# vesta_IO_buffering.net
KiCad netlist of a schematic drawn in Altium Designer
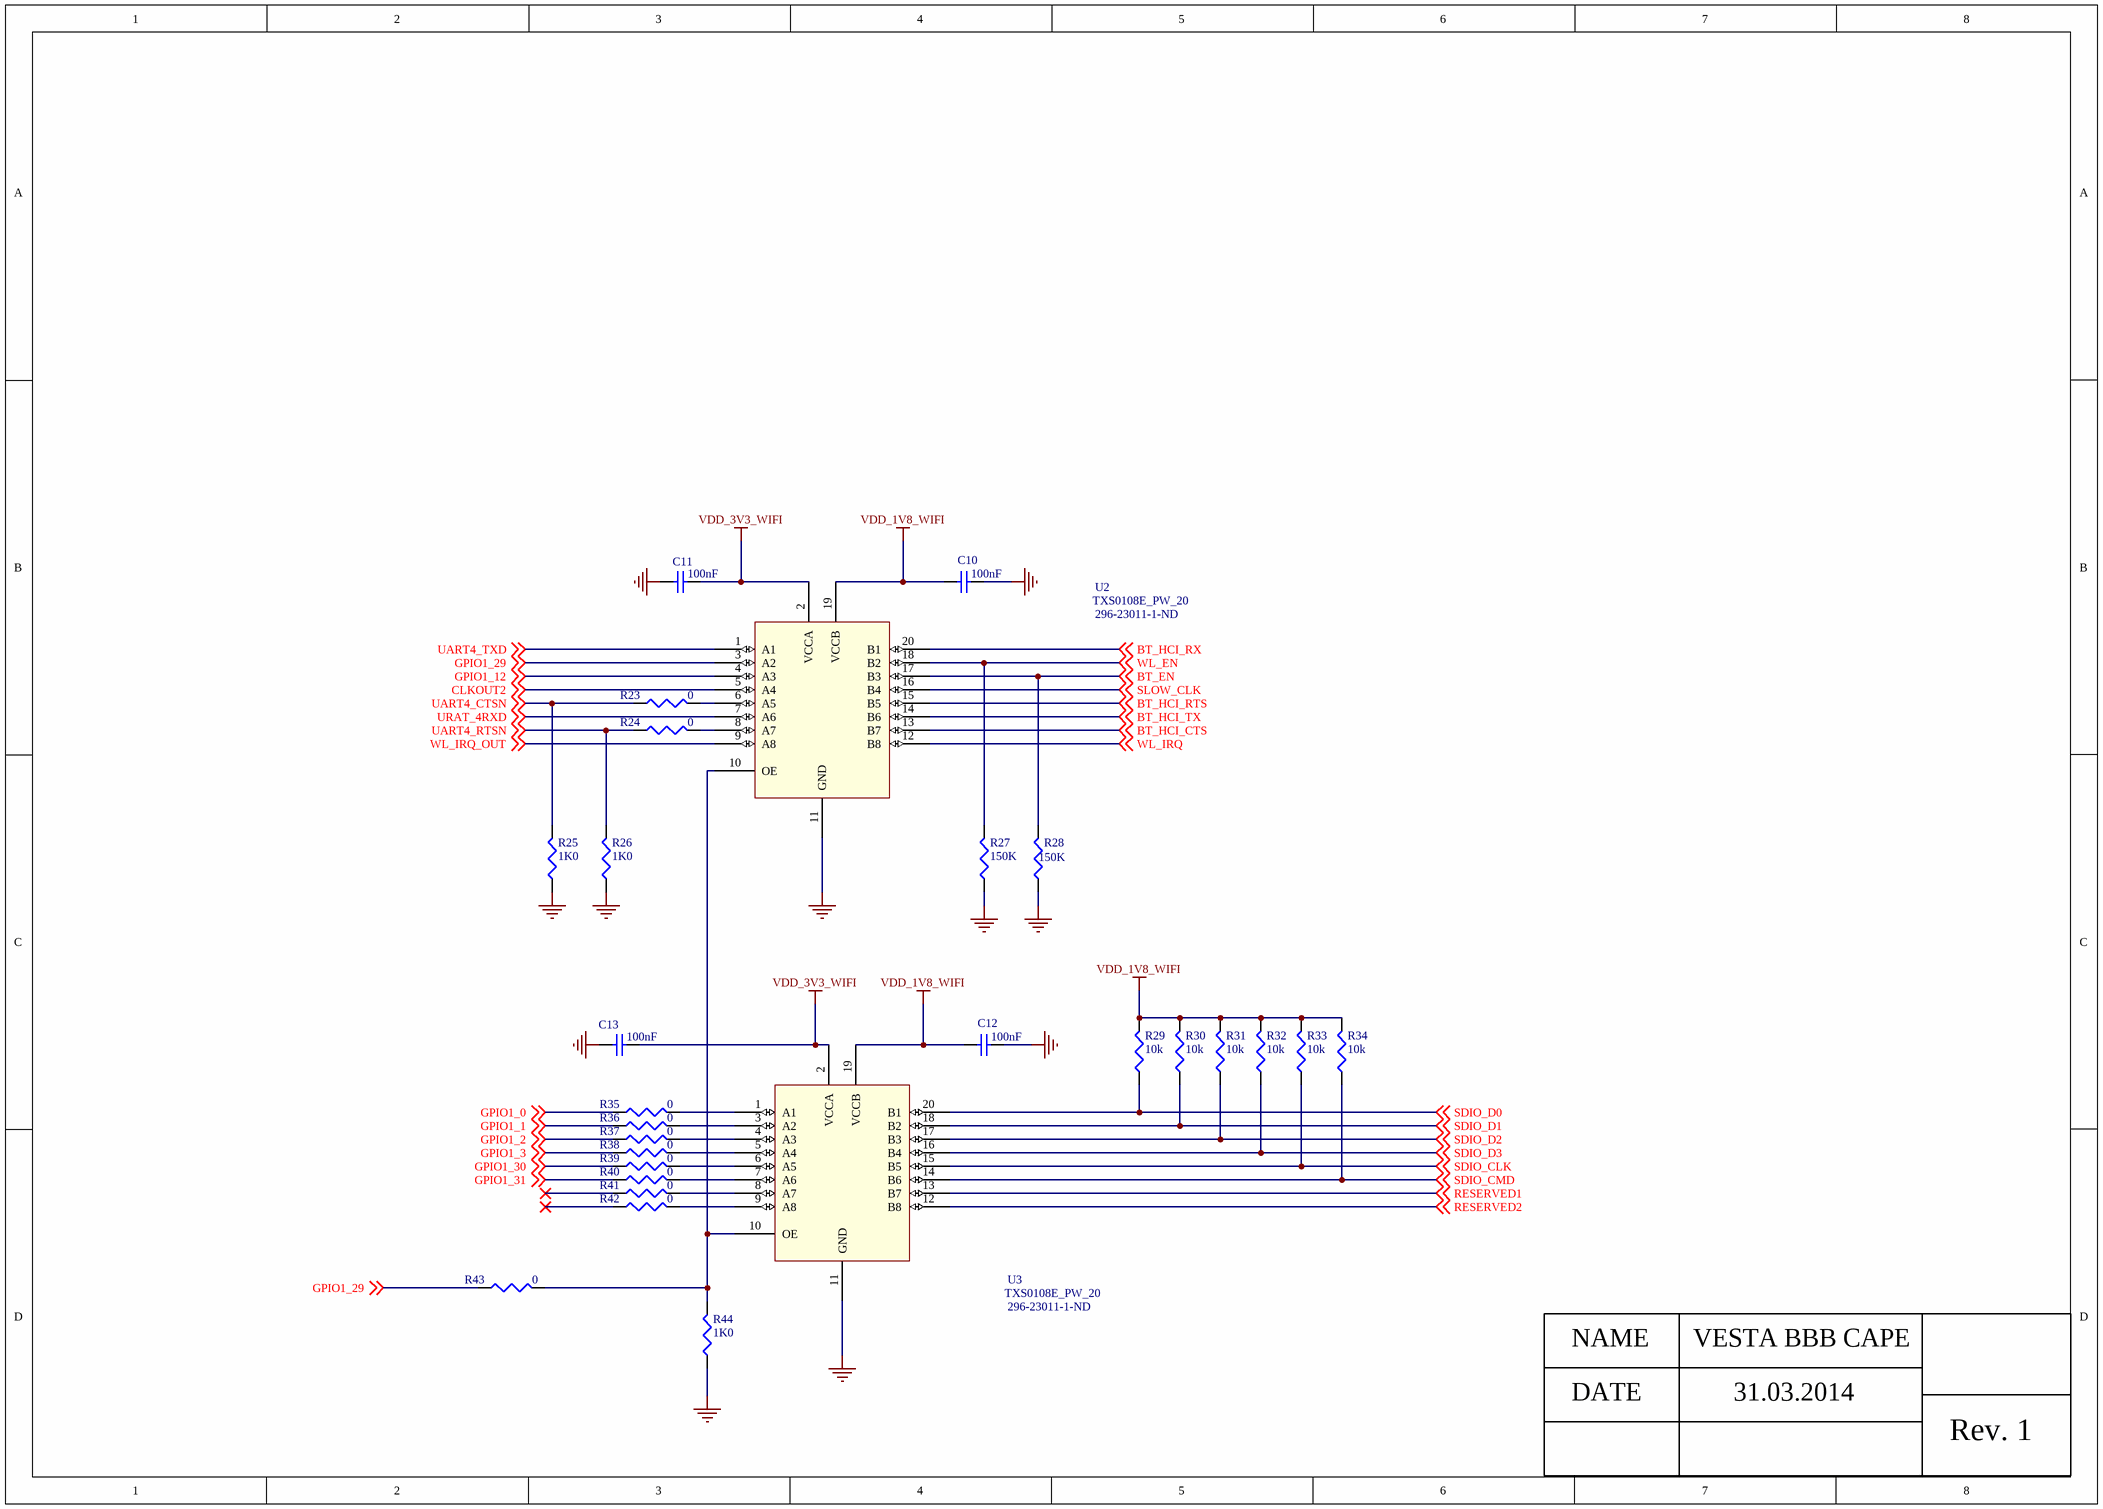
[diagram p0: vesta_IO_buffering.SchDoc]

(export (version "E")
  (design (tool "Eeschema 10.0.6"))
  (components
    (comp (ref "C10")
      (value "100nF")
      (footprint "C2512")
      (description "Capacitor (Semiconductor SIM Model)")
      (fields (field (name "Comment") "Cap Semi") (field (name "PUBLISHER") "Altium Limited"))
      (libsource (lib "Miscellaneous Devices") (part "Cap Semi"))
    )
    (comp (ref "C11")
      (value "100nF")
      (footprint "C2512")
      (description "Capacitor (Semiconductor SIM Model)")
      (fields (field (name "Comment") "Cap Semi") (field (name "PUBLISHER") "Altium Limited"))
      (libsource (lib "Miscellaneous Devices") (part "Cap Semi"))
    )
    (comp (ref "C12")
      (value "100nF")
      (footprint "C2512")
      (description "Capacitor (Semiconductor SIM Model)")
      (fields (field (name "PUBLISHER") "Altium Limited"))
      (libsource (lib "Miscellaneous Devices") (part "Cap Semi"))
    )
    (comp (ref "C13")
      (value "100nF")
      (footprint "C2512")
      (description "Capacitor (Semiconductor SIM Model)")
      (fields (field (name "PUBLISHER") "Altium Limited"))
      (libsource (lib "Miscellaneous Devices") (part "Cap Semi"))
    )
    (comp (ref "R23")
      (value "0")
      (footprint "J1-0603")
      (description "Resistor")
      (fields (field (name "PUBLISHER") "Altium Limited"))
      (libsource (lib "Miscellaneous Devices") (part "Res3"))
    )
    (comp (ref "R24")
      (value "0")
      (footprint "J1-0603")
      (description "Resistor")
      (fields (field (name "PUBLISHER") "Altium Limited"))
      (libsource (lib "Miscellaneous Devices") (part "Res3"))
    )
    (comp (ref "R25")
      (value "1K0")
      (footprint "J1-0603")
      (description "Resistor")
      (fields (field (name "PUBLISHER") "Altium Limited"))
      (libsource (lib "Miscellaneous Devices") (part "Res3"))
    )
    (comp (ref "R26")
      (value "1K0")
      (footprint "J1-0603")
      (description "Resistor")
      (fields (field (name "PUBLISHER") "Altium Limited"))
      (libsource (lib "Miscellaneous Devices") (part "Res3"))
    )
    (comp (ref "R27")
      (value "150K")
      (footprint "J1-0603")
      (description "Resistor")
      (fields (field (name "PUBLISHER") "Altium Limited"))
      (libsource (lib "Miscellaneous Devices") (part "Res3"))
    )
    (comp (ref "R28")
      (value "150K")
      (footprint "J1-0603")
      (description "Resistor")
      (fields (field (name "PUBLISHER") "Altium Limited"))
      (libsource (lib "Miscellaneous Devices") (part "Res3"))
    )
    (comp (ref "R29")
      (value "10k")
      (footprint "J1-0603")
      (description "Resistor")
      (fields (field (name "PUBLISHER") "Altium Limited"))
      (libsource (lib "Miscellaneous Devices") (part "Res3"))
    )
    (comp (ref "R30")
      (value "10k")
      (footprint "J1-0603")
      (description "Resistor")
      (fields (field (name "PUBLISHER") "Altium Limited"))
      (libsource (lib "Miscellaneous Devices") (part "Res3"))
    )
    (comp (ref "R31")
      (value "10k")
      (footprint "J1-0603")
      (description "Resistor")
      (fields (field (name "PUBLISHER") "Altium Limited"))
      (libsource (lib "Miscellaneous Devices") (part "Res3"))
    )
    (comp (ref "R32")
      (value "10k")
      (footprint "J1-0603")
      (description "Resistor")
      (fields (field (name "PUBLISHER") "Altium Limited"))
      (libsource (lib "Miscellaneous Devices") (part "Res3"))
    )
    (comp (ref "R33")
      (value "10k")
      (footprint "J1-0603")
      (description "Resistor")
      (fields (field (name "PUBLISHER") "Altium Limited"))
      (libsource (lib "Miscellaneous Devices") (part "Res3"))
    )
    (comp (ref "R34")
      (value "10k")
      (footprint "J1-0603")
      (description "Resistor")
      (fields (field (name "PUBLISHER") "Altium Limited"))
      (libsource (lib "Miscellaneous Devices") (part "Res3"))
    )
    (comp (ref "R35")
      (value "0")
      (footprint "J1-0603")
      (description "Resistor")
      (fields (field (name "PUBLISHER") "Altium Limited"))
      (libsource (lib "Miscellaneous Devices") (part "Res3"))
    )
    (comp (ref "R36")
      (value "0")
      (footprint "J1-0603")
      (description "Resistor")
      (fields (field (name "PUBLISHER") "Altium Limited"))
      (libsource (lib "Miscellaneous Devices") (part "Res3"))
    )
    (comp (ref "R37")
      (value "0")
      (footprint "J1-0603")
      (description "Resistor")
      (fields (field (name "PUBLISHER") "Altium Limited"))
      (libsource (lib "Miscellaneous Devices") (part "Res3"))
    )
    (comp (ref "R38")
      (value "0")
      (footprint "J1-0603")
      (description "Resistor")
      (fields (field (name "PUBLISHER") "Altium Limited"))
      (libsource (lib "Miscellaneous Devices") (part "Res3"))
    )
    (comp (ref "R39")
      (value "0")
      (footprint "J1-0603")
      (description "Resistor")
      (fields (field (name "PUBLISHER") "Altium Limited"))
      (libsource (lib "Miscellaneous Devices") (part "Res3"))
    )
    (comp (ref "R40")
      (value "0")
      (footprint "J1-0603")
      (description "Resistor")
      (fields (field (name "PUBLISHER") "Altium Limited"))
      (libsource (lib "Miscellaneous Devices") (part "Res3"))
    )
    (comp (ref "R41")
      (value "0")
      (footprint "J1-0603")
      (description "Resistor")
      (fields (field (name "PUBLISHER") "Altium Limited"))
      (libsource (lib "Miscellaneous Devices") (part "Res3"))
    )
    (comp (ref "R42")
      (value "0")
      (footprint "J1-0603")
      (description "Resistor")
      (fields (field (name "PUBLISHER") "Altium Limited"))
      (libsource (lib "Miscellaneous Devices") (part "Res3"))
    )
    (comp (ref "R43")
      (value "0")
      (footprint "J1-0603")
      (description "Resistor")
      (fields (field (name "PUBLISHER") "Altium Limited"))
      (libsource (lib "Miscellaneous Devices") (part "Res3"))
    )
    (comp (ref "R44")
      (value "1K0")
      (footprint "J1-0603")
      (description "Resistor")
      (fields (field (name "PUBLISHER") "Altium Limited"))
      (libsource (lib "Miscellaneous Devices") (part "Res3"))
    )
    (comp (ref "U2")
      (value "TXS0108E_PW_20")
      (footprint "TXS0108E:PW20")
      (description "Imported")
      (fields
        (field (name "MANUFACTURER_PART_NUMBER") "txs0108e_pw_20")
        (field (name "GENERIC_PART_NUMBER") "TXS0108E")
        (field (name "SUPPLIER PART NUMBER 1") "296-23011-1-ND")
      )
      (libsource (lib "TXS0108E") (part "TXS0108E_PW_20"))
    )
    (comp (ref "U3")
      (value "TXS0108E_PW_20")
      (footprint "TXS0108E:PW20")
      (description "Imported")
      (fields
        (field (name "MANUFACTURER_PART_NUMBER") "txs0108e_pw_20")
        (field (name "GENERIC_PART_NUMBER") "TXS0108E")
        (field (name "SUPPLIER PART NUMBER 1") "296-23011-1-ND")
      )
      (libsource (lib "TXS0108E") (part "TXS0108E_PW_20"))
    )
  )
  (nets
    (net (code "1") (name "BT_EN") (class "Default")
      (node (ref "R28") (pin "2") (pinfunction "2_2") (pintype "passive"))
      (node (ref "U2") (pin "17") (pinfunction "B3_17") (pintype "bidirectional"))
    )
    (net (code "2") (name "BT_HCI_CTS") (class "Default")
      (node (ref "U2") (pin "13") (pinfunction "B7_13") (pintype "bidirectional"))
    )
    (net (code "3") (name "BT_HCI_RTS") (class "Default")
      (node (ref "U2") (pin "15") (pinfunction "B5_15") (pintype "bidirectional"))
    )
    (net (code "4") (name "BT_HCI_RX") (class "Default")
      (node (ref "U2") (pin "20") (pinfunction "B1_20") (pintype "bidirectional"))
    )
    (net (code "5") (name "BT_HCI_TX") (class "Default")
      (node (ref "U2") (pin "14") (pinfunction "B6_14") (pintype "bidirectional"))
    )
    (net (code "6") (name "CLKOUT2") (class "Default")
      (node (ref "U2") (pin "5") (pinfunction "A4_5") (pintype "bidirectional"))
    )
    (net (code "7") (name "GND") (class "Default")
      (node (ref "C10") (pin "2") (pinfunction "2_2") (pintype "passive"))
      (node (ref "C11") (pin "1") (pinfunction "1_1") (pintype "passive"))
      (node (ref "C12") (pin "2") (pinfunction "2_2") (pintype "passive"))
      (node (ref "C13") (pin "1") (pinfunction "1_1") (pintype "passive"))
      (node (ref "R25") (pin "1") (pinfunction "1_1") (pintype "passive"))
      (node (ref "R26") (pin "1") (pinfunction "1_1") (pintype "passive"))
      (node (ref "R27") (pin "1") (pinfunction "1_1") (pintype "passive"))
      (node (ref "R28") (pin "1") (pinfunction "1_1") (pintype "passive"))
      (node (ref "R44") (pin "1") (pinfunction "1_1") (pintype "passive"))
      (node (ref "U2") (pin "11") (pinfunction "GND_11") (pintype "power_in"))
      (node (ref "U3") (pin "11") (pinfunction "GND_11") (pintype "power_in"))
    )
    (net (code "8") (name "GPIO1_0") (class "Default")
      (node (ref "R35") (pin "1") (pinfunction "1_1") (pintype "passive"))
    )
    (net (code "9") (name "GPIO1_1") (class "Default")
      (node (ref "R36") (pin "1") (pinfunction "1_1") (pintype "passive"))
    )
    (net (code "10") (name "GPIO1_2") (class "Default")
      (node (ref "R37") (pin "1") (pinfunction "1_1") (pintype "passive"))
    )
    (net (code "11") (name "GPIO1_3") (class "Default")
      (node (ref "R38") (pin "1") (pinfunction "1_1") (pintype "passive"))
    )
    (net (code "12") (name "GPIO1_12") (class "Default")
      (node (ref "U2") (pin "4") (pinfunction "A3_4") (pintype "bidirectional"))
    )
    (net (code "13") (name "GPIO1_29") (class "Default")
      (node (ref "R43") (pin "1") (pinfunction "1_1") (pintype "passive"))
      (node (ref "U2") (pin "3") (pinfunction "A2_3") (pintype "bidirectional"))
    )
    (net (code "14") (name "GPIO1_30") (class "Default")
      (node (ref "R39") (pin "1") (pinfunction "1_1") (pintype "passive"))
    )
    (net (code "15") (name "GPIO1_31") (class "Default")
      (node (ref "R40") (pin "1") (pinfunction "1_1") (pintype "passive"))
    )
    (net (code "16") (name "Net-(U2-A5)") (class "Default")
      (node (ref "R23") (pin "2") (pinfunction "2_2") (pintype "passive"))
      (node (ref "U2") (pin "6") (pinfunction "A5_6") (pintype "bidirectional"))
    )
    (net (code "17") (name "Net-(U2-A7)") (class "Default")
      (node (ref "R24") (pin "2") (pinfunction "2_2") (pintype "passive"))
      (node (ref "U2") (pin "8") (pinfunction "A7_8") (pintype "bidirectional"))
    )
    (net (code "18") (name "Net-(U2-OE)") (class "Default")
      (node (ref "R43") (pin "2") (pinfunction "2_2") (pintype "passive"))
      (node (ref "R44") (pin "2") (pinfunction "2_2") (pintype "passive"))
      (node (ref "U2") (pin "10") (pinfunction "OE_10") (pintype "passive"))
      (node (ref "U3") (pin "10") (pinfunction "OE_10") (pintype "passive"))
    )
    (net (code "19") (name "Net-(U3-A1)") (class "Default")
      (node (ref "R35") (pin "2") (pinfunction "2_2") (pintype "passive"))
      (node (ref "U3") (pin "1") (pinfunction "A1_1") (pintype "bidirectional"))
    )
    (net (code "20") (name "Net-(U3-A2)") (class "Default")
      (node (ref "R36") (pin "2") (pinfunction "2_2") (pintype "passive"))
      (node (ref "U3") (pin "3") (pinfunction "A2_3") (pintype "bidirectional"))
    )
    (net (code "21") (name "Net-(U3-A3)") (class "Default")
      (node (ref "R37") (pin "2") (pinfunction "2_2") (pintype "passive"))
      (node (ref "U3") (pin "4") (pinfunction "A3_4") (pintype "bidirectional"))
    )
    (net (code "22") (name "Net-(U3-A4)") (class "Default")
      (node (ref "R38") (pin "2") (pinfunction "2_2") (pintype "passive"))
      (node (ref "U3") (pin "5") (pinfunction "A4_5") (pintype "bidirectional"))
    )
    (net (code "23") (name "Net-(U3-A5)") (class "Default")
      (node (ref "R39") (pin "2") (pinfunction "2_2") (pintype "passive"))
      (node (ref "U3") (pin "6") (pinfunction "A5_6") (pintype "bidirectional"))
    )
    (net (code "24") (name "Net-(U3-A6)") (class "Default")
      (node (ref "R40") (pin "2") (pinfunction "2_2") (pintype "passive"))
      (node (ref "U3") (pin "7") (pinfunction "A6_7") (pintype "bidirectional"))
    )
    (net (code "25") (name "Net-(U3-A7)") (class "Default")
      (node (ref "R41") (pin "2") (pinfunction "2_2") (pintype "passive"))
      (node (ref "U3") (pin "8") (pinfunction "A7_8") (pintype "bidirectional"))
    )
    (net (code "26") (name "Net-(U3-A8)") (class "Default")
      (node (ref "R42") (pin "2") (pinfunction "2_2") (pintype "passive"))
      (node (ref "U3") (pin "9") (pinfunction "A8_9") (pintype "bidirectional"))
    )
    (net (code "27") (name "RESERVED1") (class "Default")
      (node (ref "U3") (pin "13") (pinfunction "B7_13") (pintype "bidirectional"))
    )
    (net (code "28") (name "RESERVED2") (class "Default")
      (node (ref "U3") (pin "12") (pinfunction "B8_12") (pintype "bidirectional"))
    )
    (net (code "29") (name "SDIO_CLK") (class "Default")
      (node (ref "R33") (pin "1") (pinfunction "1_1") (pintype "passive"))
      (node (ref "U3") (pin "15") (pinfunction "B5_15") (pintype "bidirectional"))
    )
    (net (code "30") (name "SDIO_CMD") (class "Default")
      (node (ref "R34") (pin "1") (pinfunction "1_1") (pintype "passive"))
      (node (ref "U3") (pin "14") (pinfunction "B6_14") (pintype "bidirectional"))
    )
    (net (code "31") (name "SDIO_D0") (class "Default")
      (node (ref "R29") (pin "1") (pinfunction "1_1") (pintype "passive"))
      (node (ref "U3") (pin "20") (pinfunction "B1_20") (pintype "bidirectional"))
    )
    (net (code "32") (name "SDIO_D1") (class "Default")
      (node (ref "R30") (pin "1") (pinfunction "1_1") (pintype "passive"))
      (node (ref "U3") (pin "18") (pinfunction "B2_18") (pintype "bidirectional"))
    )
    (net (code "33") (name "SDIO_D2") (class "Default")
      (node (ref "R31") (pin "1") (pinfunction "1_1") (pintype "passive"))
      (node (ref "U3") (pin "17") (pinfunction "B3_17") (pintype "bidirectional"))
    )
    (net (code "34") (name "SDIO_D3") (class "Default")
      (node (ref "R32") (pin "1") (pinfunction "1_1") (pintype "passive"))
      (node (ref "U3") (pin "16") (pinfunction "B4_16") (pintype "bidirectional"))
    )
    (net (code "35") (name "SLOW_CLK") (class "Default")
      (node (ref "U2") (pin "16") (pinfunction "B4_16") (pintype "bidirectional"))
    )
    (net (code "36") (name "UART4_CTSN") (class "Default")
      (node (ref "R23") (pin "1") (pinfunction "1_1") (pintype "passive"))
      (node (ref "R25") (pin "2") (pinfunction "2_2") (pintype "passive"))
    )
    (net (code "37") (name "UART4_RTSN") (class "Default")
      (node (ref "R24") (pin "1") (pinfunction "1_1") (pintype "passive"))
      (node (ref "R26") (pin "2") (pinfunction "2_2") (pintype "passive"))
    )
    (net (code "38") (name "UART4_TXD") (class "Default")
      (node (ref "U2") (pin "1") (pinfunction "A1_1") (pintype "bidirectional"))
    )
    (net (code "39") (name "URAT_4RXD") (class "Default")
      (node (ref "U2") (pin "7") (pinfunction "A6_7") (pintype "bidirectional"))
    )
    (net (code "40") (name "VDD_1V8_WIFI") (class "Default")
      (node (ref "C10") (pin "1") (pinfunction "1_1") (pintype "passive"))
      (node (ref "C12") (pin "1") (pinfunction "1_1") (pintype "passive"))
      (node (ref "R29") (pin "2") (pinfunction "2_2") (pintype "passive"))
      (node (ref "R30") (pin "2") (pinfunction "2_2") (pintype "passive"))
      (node (ref "R31") (pin "2") (pinfunction "2_2") (pintype "passive"))
      (node (ref "R32") (pin "2") (pinfunction "2_2") (pintype "passive"))
      (node (ref "R33") (pin "2") (pinfunction "2_2") (pintype "passive"))
      (node (ref "R34") (pin "2") (pinfunction "2_2") (pintype "passive"))
      (node (ref "U2") (pin "19") (pinfunction "VCCB_19") (pintype "power_in"))
      (node (ref "U3") (pin "19") (pinfunction "VCCB_19") (pintype "power_in"))
    )
    (net (code "41") (name "VDD_3V3_WIFI") (class "Default")
      (node (ref "C11") (pin "2") (pinfunction "2_2") (pintype "passive"))
      (node (ref "C13") (pin "2") (pinfunction "2_2") (pintype "passive"))
      (node (ref "U2") (pin "2") (pinfunction "VCCA_2") (pintype "power_in"))
      (node (ref "U3") (pin "2") (pinfunction "VCCA_2") (pintype "power_in"))
    )
    (net (code "42") (name "WL_EN") (class "Default")
      (node (ref "R27") (pin "2") (pinfunction "2_2") (pintype "passive"))
      (node (ref "U2") (pin "18") (pinfunction "B2_18") (pintype "bidirectional"))
    )
    (net (code "43") (name "WL_IRQ") (class "Default")
      (node (ref "U2") (pin "12") (pinfunction "B8_12") (pintype "bidirectional"))
    )
    (net (code "44") (name "WL_IRQ_OUT") (class "Default")
      (node (ref "U2") (pin "9") (pinfunction "A8_9") (pintype "bidirectional"))
    )
    (net (code "45") (name "unconnected-(R41-Pad1)") (class "Default")
      (node (ref "R41") (pin "1") (pinfunction "1_1") (pintype "passive+no_connect"))
    )
    (net (code "46") (name "unconnected-(R42-Pad1)") (class "Default")
      (node (ref "R42") (pin "1") (pinfunction "1_1") (pintype "passive+no_connect"))
    )
  )
)
